# PX4FMUv2_4_6_9.net
KiCad netlist of a schematic drawn in Altium Designer
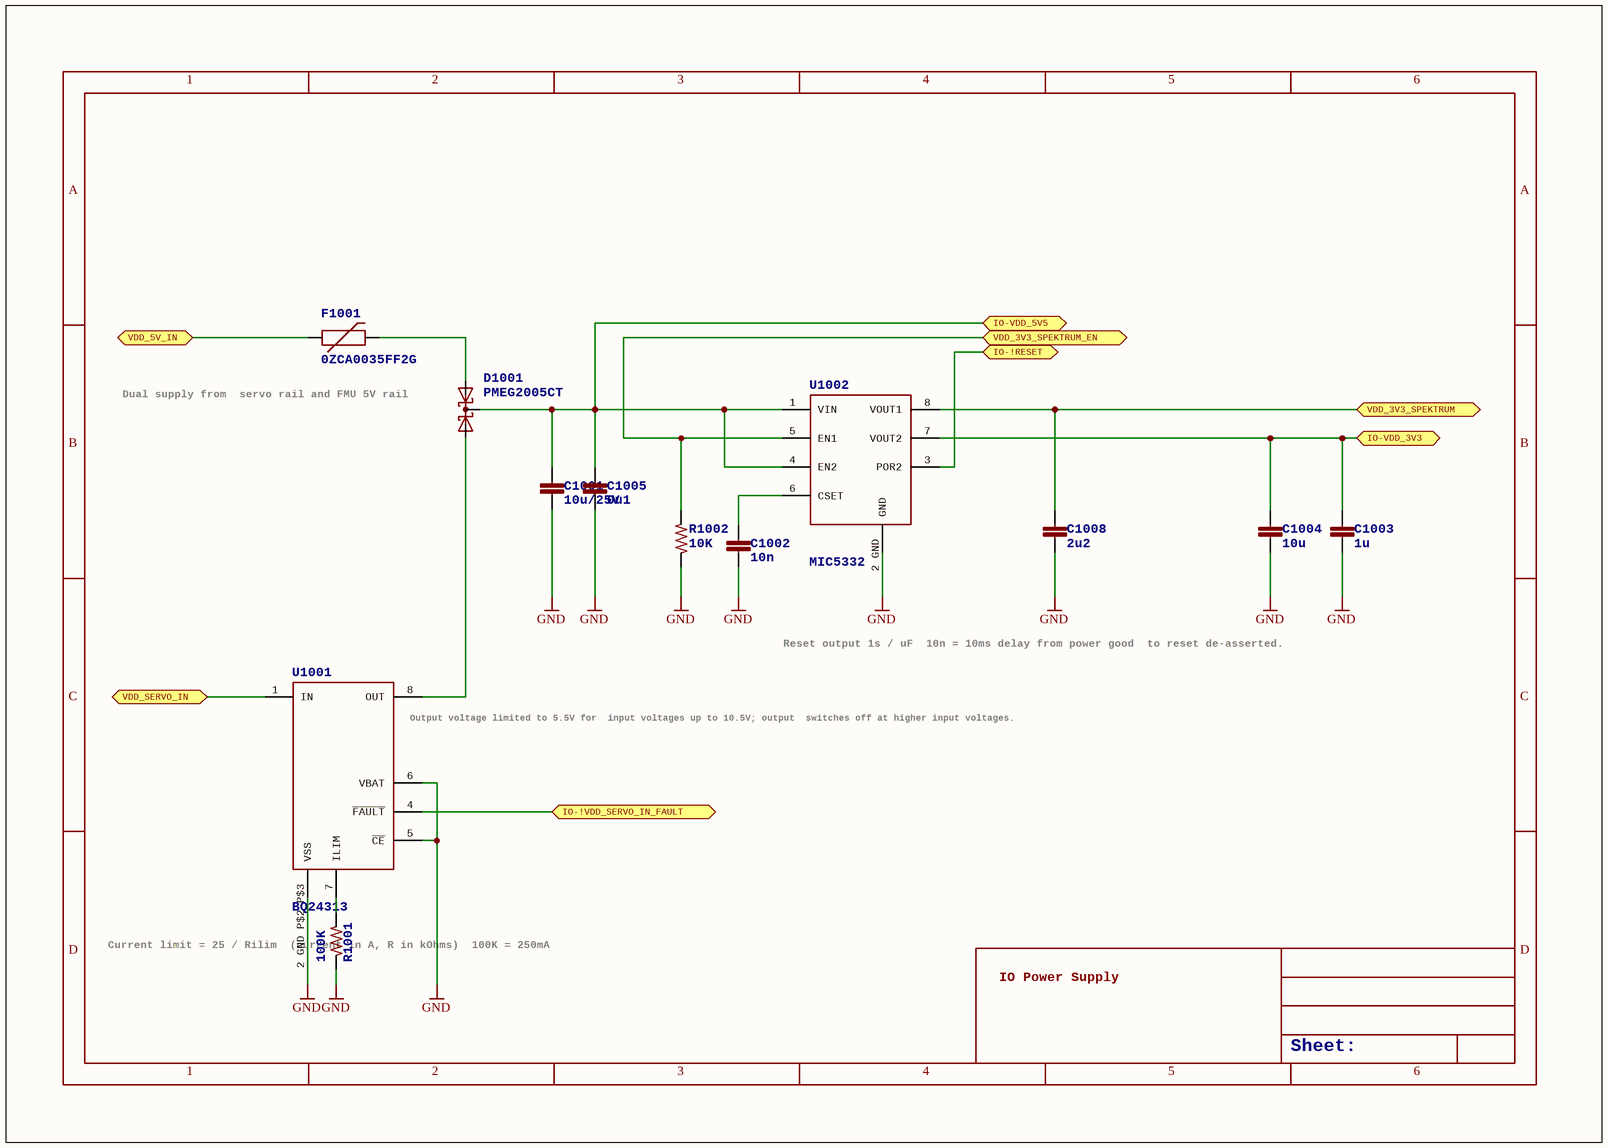
[diagram p0: PX4FMUv2.4.6_9.SchDoc]

(export (version "E")
  (design (tool "Eeschema 10.0.6"))
  (components
    (comp (ref "C1001")
      (value "10u/25V")
      (footprint "0805-CAP")
      (description "CapacitorStandard 0603 ceramic capacitor, and 0.1\" leaded capacitor.")
      (fields (field (name "PARTNO") "CL21A106KAYNNNE"))
      (libsource (lib "pixhawk2") (part "CAP0805"))
    )
    (comp (ref "C1002")
      (value "10n")
      (footprint "0402-CAP")
      (description "CapacitorStandard 0603 ceramic capacitor, and 0.1\" leaded capacitor.")
      (fields (field (name "PARTNO") "CC0402KRX7R7BB103"))
      (libsource (lib "pixhawk2") (part "CAP0402"))
    )
    (comp (ref "C1003")
      (value "1u")
      (footprint "0603-CAP")
      (description "CapacitorStandard 0603 ceramic capacitor, and 0.1\" leaded capacitor.")
      (fields (field (name "PARTNO") "CC0603ZRY5V7BB105"))
      (libsource (lib "pixhawk2") (part "CAP0603"))
    )
    (comp (ref "C1004")
      (value "10u")
      (footprint "0603-CAP")
      (description "CapacitorStandard 0603 ceramic capacitor, and 0.1\" leaded capacitor.")
      (fields (field (name "PARTNO") "C1608X5R1A106K080AC"))
      (libsource (lib "pixhawk2") (part "CAP0603"))
    )
    (comp (ref "C1005")
      (value "0u1")
      (footprint "0402-CAP")
      (description "CapacitorStandard 0603 ceramic capacitor, and 0.1\" leaded capacitor.")
      (fields (field (name "PARTNO") "CC0402ZRY5V7BB104"))
      (libsource (lib "pixhawk2") (part "CAP0402"))
    )
    (comp (ref "C1008")
      (value "2u2")
      (footprint "0402-CAP")
      (description "CapacitorStandard 0603 ceramic capacitor, and 0.1\" leaded capacitor.")
      (fields (field (name "PARTNO") "C1005X6S1C225K050BC"))
      (libsource (lib "pixhawk2") (part "CAP0402"))
    )
    (comp (ref "D1001")
      (value "PMEG2005CT")
      (footprint "SOT23-3")
      (libsource (lib "pixhawk2") (part "PMEG2005CT"))
    )
    (comp (ref "F1001")
      (value "0ZCA0035FF2G")
      (footprint "PTC-1206")
      (description "Resettable Fuse PTCResettable Fuse. Spark Fun Electronics SKU : COM-08357")
      (libsource (lib "pixhawk2") (part "PTCSMD"))
    )
    (comp (ref "R1001")
      (value "100K")
      (footprint "0402-RES")
      (libsource (lib "pixhawk2") (part "RESISTOR0402-RES"))
    )
    (comp (ref "R1002")
      (value "10K")
      (footprint "0402-RES")
      (fields (field (name "PARTNO") "RC0402FR-0710KL"))
      (libsource (lib "pixhawk2") (part "RESISTOR0402-RES"))
    )
    (comp (ref "U1001")
      (value "BQ24313")
      (footprint "QFN8-DSG")
      (fields (field (name "PARTNO") "BQ24313DSGT"))
      (libsource (lib "pixhawk2") (part "BQ24313"))
    )
    (comp (ref "U1002")
      (value "MIC5332")
      (footprint "MLF-8-EPAD")
      (fields (field (name "PARTNO") "MIC5332-SSYMT"))
      (libsource (lib "pixhawk2") (part "MIC5332"))
    )
  )
  (nets
    (net (code "1") (name "/IO-!RESET") (class "Default")
      (node (ref "U1002") (pin "3") (pinfunction "POR2_3") (pintype "passive"))
    )
    (net (code "2") (name "/IO-!VDD_SERVO_IN_FAULT") (class "Default")
      (node (ref "U1001") (pin "4") (pinfunction "~{FAULT}_4") (pintype "passive"))
    )
    (net (code "3") (name "/IO-VDD_3V3") (class "Default")
      (node (ref "C1003") (pin "P$1") (pinfunction "1_P$1") (pintype "passive"))
      (node (ref "C1004") (pin "P$1") (pinfunction "1_P$1") (pintype "passive"))
      (node (ref "U1002") (pin "7") (pinfunction "VOUT2_7") (pintype "passive"))
    )
    (net (code "4") (name "/IO-VDD_5V5") (class "Default")
      (node (ref "C1001") (pin "P$1") (pinfunction "1_P$1") (pintype "passive"))
      (node (ref "C1005") (pin "P$1") (pinfunction "1_P$1") (pintype "passive"))
      (node (ref "D1001") (pin "3") (pinfunction "CC_3") (pintype "passive"))
      (node (ref "U1002") (pin "1") (pinfunction "VIN_1") (pintype "passive"))
      (node (ref "U1002") (pin "4") (pinfunction "EN2_4") (pintype "passive"))
    )
    (net (code "5") (name "/VDD_3V3_SPEKTRUM") (class "Default")
      (node (ref "C1008") (pin "P$1") (pinfunction "1_P$1") (pintype "passive"))
      (node (ref "U1002") (pin "8") (pinfunction "VOUT1_8") (pintype "passive"))
    )
    (net (code "6") (name "/VDD_3V3_SPEKTRUM_EN") (class "Default")
      (node (ref "R1002") (pin "P$2") (pinfunction "2_P$2") (pintype "passive"))
      (node (ref "U1002") (pin "5") (pinfunction "EN1_5") (pintype "passive"))
    )
    (net (code "7") (name "/VDD_5V_IN") (class "Default")
      (node (ref "F1001") (pin "1") (pinfunction "1_1") (pintype "passive"))
    )
    (net (code "8") (name "/VDD_SERVO_IN") (class "Default")
      (node (ref "U1001") (pin "1") (pinfunction "IN_1") (pintype "passive"))
    )
    (net (code "9") (name "GND") (class "Default")
      (node (ref "C1001") (pin "P$2") (pinfunction "2_P$2") (pintype "passive"))
      (node (ref "C1002") (pin "P$2") (pinfunction "2_P$2") (pintype "passive"))
      (node (ref "C1003") (pin "P$2") (pinfunction "2_P$2") (pintype "passive"))
      (node (ref "C1004") (pin "P$2") (pinfunction "2_P$2") (pintype "passive"))
      (node (ref "C1005") (pin "P$2") (pinfunction "2_P$2") (pintype "passive"))
      (node (ref "C1008") (pin "P$2") (pinfunction "2_P$2") (pintype "passive"))
      (node (ref "R1001") (pin "P$1") (pinfunction "1_P$1") (pintype "passive"))
      (node (ref "R1002") (pin "P$1") (pinfunction "1_P$1") (pintype "passive"))
      (node (ref "U1001") (pin "2_GND_P$2_P$3") (pinfunction "VSS_2_GND_P$2_P$3") (pintype "passive"))
      (node (ref "U1001") (pin "5") (pinfunction "~{CE}_5") (pintype "passive"))
      (node (ref "U1001") (pin "6") (pinfunction "VBAT_6") (pintype "passive"))
      (node (ref "U1002") (pin "2_GND") (pinfunction "GND_2_GND") (pintype "passive"))
    )
    (net (code "10") (name "Net-(C1002-1)") (class "Default")
      (node (ref "C1002") (pin "P$1") (pinfunction "1_P$1") (pintype "passive"))
      (node (ref "U1002") (pin "6") (pinfunction "CSET_6") (pintype "passive"))
    )
    (net (code "11") (name "Net-(D1001-A1)") (class "Default")
      (node (ref "D1001") (pin "1") (pinfunction "A1_1") (pintype "passive"))
      (node (ref "F1001") (pin "2") (pinfunction "2_2") (pintype "passive"))
    )
    (net (code "12") (name "Net-(D1001-A2)") (class "Default")
      (node (ref "D1001") (pin "2") (pinfunction "A2_2") (pintype "passive"))
      (node (ref "U1001") (pin "8") (pinfunction "OUT_8") (pintype "passive"))
    )
    (net (code "13") (name "Net-(R1001-2)") (class "Default")
      (node (ref "R1001") (pin "P$2") (pinfunction "2_P$2") (pintype "passive"))
      (node (ref "U1001") (pin "7") (pinfunction "ILIM_7") (pintype "passive"))
    )
  )
)
